# buck.net
KiCad netlist of a schematic drawn in EAGLE
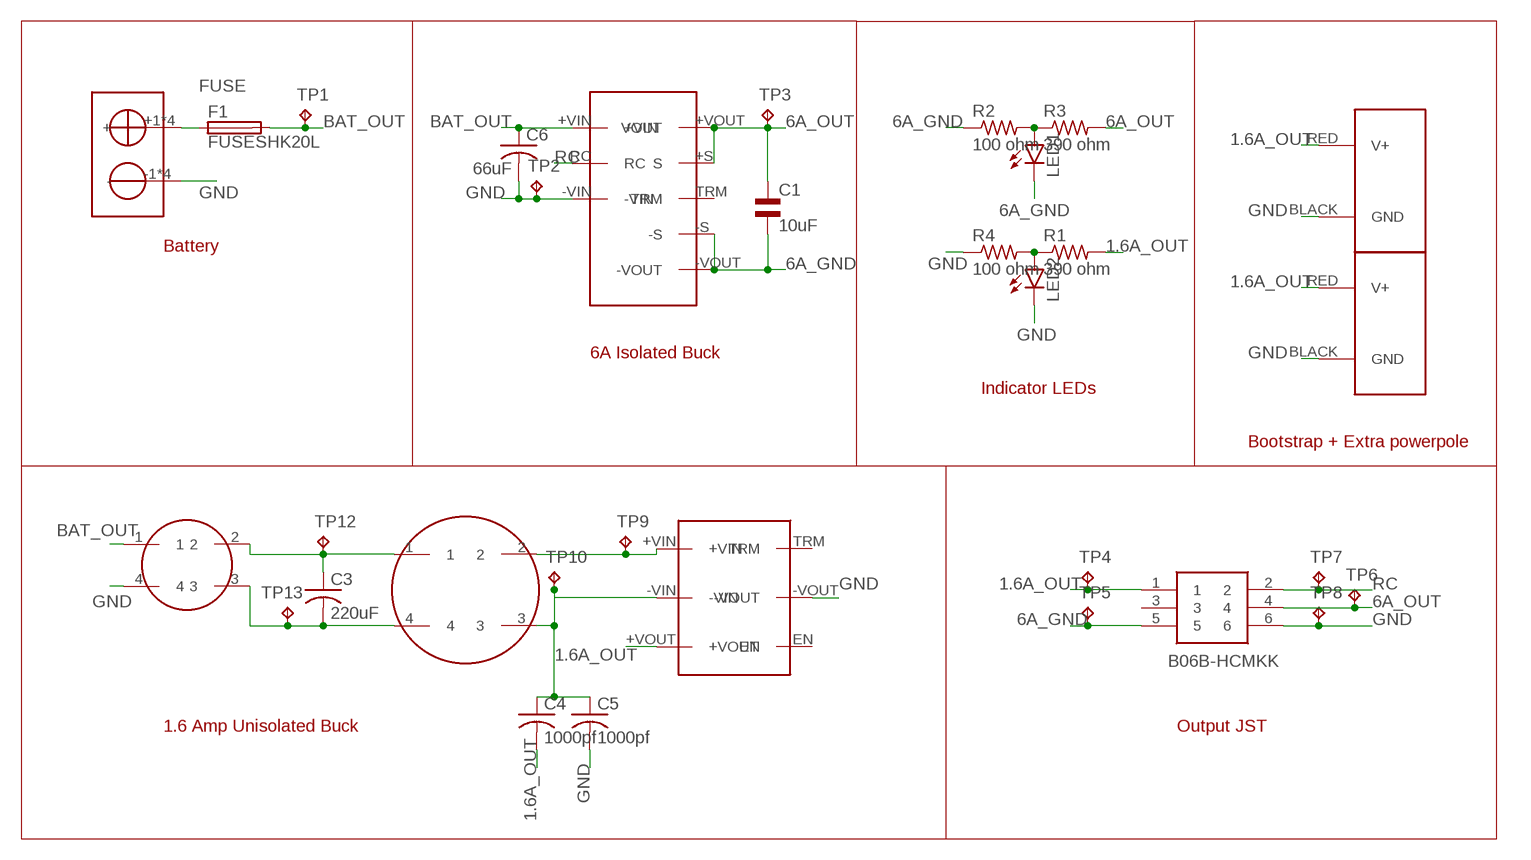
[diagram p0: schematic, sheet 1]

(export (version "E")
  (design (tool "Eeschema 10.0.6"))
  (components
    (comp (ref "BUCK150UH")
      (value "CMNMODECHOKE150UH")
      (footprint "eagle-import:CMNMODECHOKE150UH")
      (libsource (lib "eagle-import") (part "CMNMODECHOKE150UH"))
    )
    (comp (ref "C1")
      (value "10uF")
      (footprint "eagle-import:EU25-10")
      (libsource (lib "eagle-import") (part "EL-BI25-10AXIAL"))
    )
    (comp (ref "C3")
      (value "220uF")
      (footprint "eagle-import:C0805")
      (libsource (lib "eagle-import") (part "C-USC0805"))
    )
    (comp (ref "C4")
      (value "1000pf")
      (footprint "eagle-import:C0805")
      (libsource (lib "eagle-import") (part "C-USC0805"))
    )
    (comp (ref "C5")
      (value "1000pf")
      (footprint "eagle-import:C0805")
      (libsource (lib "eagle-import") (part "C-USC0805"))
    )
    (comp (ref "C6")
      (value "66uF")
      (footprint "eagle-import:C0805")
      (libsource (lib "eagle-import") (part "C-USC0805"))
    )
    (comp (ref "CHOKEME")
      (value "CMNMODECHOKE1.2MH")
      (footprint "eagle-import:CMNMODECHOKE1.2MH")
      (libsource (lib "eagle-import") (part "CMNMODECHOKE1.2MH"))
    )
    (comp (ref "F1")
      (value "FUSESHK20L")
      (footprint "eagle-import:SHK20L")
      (libsource (lib "eagle-import") (part "FUSESHK20L"))
    )
    (comp (ref "J1")
      (value "B06B-HCMKK")
      (footprint "eagle-import:B06BHCMKK")
      (fields (field (name "MOUSER_PART_NUMBER") "306-B06B-HCMKK"))
      (libsource (lib "eagle-import") (part "B06B-HCMKK"))
    )
    (comp (ref "J2")
      (value "POWERPOLE_POWER45A_DRILL")
      (footprint "eagle-import:POWERPOLE_PAIR_45A_HOLE")
      (libsource (lib "eagle-import") (part "POWERPOLE_POWER45A_DRILL"))
    )
    (comp (ref "J3")
      (value "POWERPOLE_POWER45A_DRILL")
      (footprint "eagle-import:POWERPOLE_PAIR_45A_HOLE")
      (libsource (lib "eagle-import") (part "POWERPOLE_POWER45A_DRILL"))
    )
    (comp (ref "LED1")
      (value "LEDCHIP-LED0603")
      (footprint "eagle-import:CHIP-LED0603")
      (libsource (lib "eagle-import") (part "LEDCHIP-LED0603"))
    )
    (comp (ref "LED2")
      (value "LEDCHIP-LED0603")
      (footprint "eagle-import:CHIP-LED0603")
      (libsource (lib "eagle-import") (part "LEDCHIP-LED0603"))
    )
    (comp (ref "R1")
      (value "390 ohm")
      (footprint "eagle-import:R0805")
      (libsource (lib "eagle-import") (part "R-US_R0805"))
    )
    (comp (ref "R2")
      (value "100 ohm")
      (footprint "eagle-import:R0805")
      (libsource (lib "eagle-import") (part "R-US_R0805"))
    )
    (comp (ref "R3")
      (value "390 ohm")
      (footprint "eagle-import:R0805")
      (libsource (lib "eagle-import") (part "R-US_R0805"))
    )
    (comp (ref "R4")
      (value "100 ohm")
      (footprint "eagle-import:R0805")
      (libsource (lib "eagle-import") (part "R-US_R0805"))
    )
    (comp (ref "TP1")
      (value "TPPAD1-13")
      (footprint "eagle-import:P1-13")
      (libsource (lib "eagle-import") (part "TPPAD1-13"))
    )
    (comp (ref "TP2")
      (value "TPPAD1-13")
      (footprint "eagle-import:P1-13")
      (libsource (lib "eagle-import") (part "TPPAD1-13"))
    )
    (comp (ref "TP3")
      (value "TPPAD1-13")
      (footprint "eagle-import:P1-13")
      (libsource (lib "eagle-import") (part "TPPAD1-13"))
    )
    (comp (ref "TP4")
      (value "TPPAD1-13")
      (footprint "eagle-import:P1-13")
      (libsource (lib "eagle-import") (part "TPPAD1-13"))
    )
    (comp (ref "TP5")
      (value "TPPAD1-13")
      (footprint "eagle-import:P1-13")
      (libsource (lib "eagle-import") (part "TPPAD1-13"))
    )
    (comp (ref "TP6")
      (value "TPPAD1-13")
      (footprint "eagle-import:P1-13")
      (libsource (lib "eagle-import") (part "TPPAD1-13"))
    )
    (comp (ref "TP7")
      (value "TPPAD1-13")
      (footprint "eagle-import:P1-13")
      (libsource (lib "eagle-import") (part "TPPAD1-13"))
    )
    (comp (ref "TP8")
      (value "TPPAD1-13")
      (footprint "eagle-import:P1-13")
      (libsource (lib "eagle-import") (part "TPPAD1-13"))
    )
    (comp (ref "TP9")
      (value "TPPAD1-13")
      (footprint "eagle-import:P1-13")
      (libsource (lib "eagle-import") (part "TPPAD1-13"))
    )
    (comp (ref "TP10")
      (value "TPPAD1-13")
      (footprint "eagle-import:P1-13")
      (libsource (lib "eagle-import") (part "TPPAD1-13"))
    )
    (comp (ref "TP12")
      (value "TPPAD1-13")
      (footprint "eagle-import:P1-13")
      (libsource (lib "eagle-import") (part "TPPAD1-13"))
    )
    (comp (ref "TP13")
      (value "TPPAD1-13")
      (footprint "eagle-import:P1-13")
      (libsource (lib "eagle-import") (part "TPPAD1-13"))
    )
    (comp (ref "U$1")
      (value "12V6ABUCKCONVERTER")
      (footprint "eagle-import:12V6ABUCKCONVERTER")
      (libsource (lib "eagle-import") (part "12V6ABUCKCONVERTER"))
    )
    (comp (ref "U$2")
      (value "SB50")
      (footprint "eagle-import:MINI-SB-50")
      (libsource (lib "eagle-import") (part "SB50"))
    )
    (comp (ref "U$3")
      (value "BUCK1.6A")
      (footprint "eagle-import:BUCK1.6A")
      (libsource (lib "eagle-import") (part "BUCK1.6A"))
    )
  )
  (nets
    (net (code "1") (name "/1.6A_OUT") (class "Default")
      (node (ref "C4") (pin "2") (pinfunction "2_2") (pintype "passive"))
      (node (ref "J1") (pin "1") (pinfunction "1_1") (pintype "bidirectional"))
      (node (ref "J2") (pin "RED") (pinfunction "V+_RED") (pintype "power_in"))
      (node (ref "J3") (pin "RED") (pinfunction "V+_RED") (pintype "power_in"))
      (node (ref "R1") (pin "2") (pinfunction "2_2") (pintype "passive"))
      (node (ref "TP4") (pin "TP") (pinfunction "TP_TP") (pintype "input"))
      (node (ref "U$3") (pin "+VOUT") (pinfunction "+VOUT_+VOUT") (pintype "bidirectional"))
    )
    (net (code "2") (name "/6A_GND") (class "Default")
      (node (ref "C1") (pin "2") (pinfunction "2_2") (pintype "passive"))
      (node (ref "J1") (pin "5") (pinfunction "5_5") (pintype "bidirectional"))
      (node (ref "LED1") (pin "C") (pinfunction "C_C") (pintype "passive"))
      (node (ref "R2") (pin "1") (pinfunction "1_1") (pintype "passive"))
      (node (ref "TP5") (pin "TP") (pinfunction "TP_TP") (pintype "input"))
      (node (ref "U$1") (pin "-S") (pinfunction "-S_-S") (pintype "bidirectional"))
      (node (ref "U$1") (pin "-VOUT") (pinfunction "-VOUT_-VOUT") (pintype "bidirectional"))
    )
    (net (code "3") (name "/6A_OUT") (class "Default")
      (node (ref "C1") (pin "1") (pinfunction "1_1") (pintype "passive"))
      (node (ref "J1") (pin "4") (pinfunction "4_4") (pintype "bidirectional"))
      (node (ref "R3") (pin "2") (pinfunction "2_2") (pintype "passive"))
      (node (ref "TP3") (pin "TP") (pinfunction "TP_TP") (pintype "input"))
      (node (ref "TP6") (pin "TP") (pinfunction "TP_TP") (pintype "input"))
      (node (ref "U$1") (pin "+S") (pinfunction "S_+S") (pintype "bidirectional"))
      (node (ref "U$1") (pin "+VOUT") (pinfunction "VOUT_+VOUT") (pintype "bidirectional"))
    )
    (net (code "4") (name "/BAT_OUT") (class "Default")
      (node (ref "BUCK150UH") (pin "1") (pinfunction "1_1") (pintype "bidirectional"))
      (node (ref "C6") (pin "1") (pinfunction "1_1") (pintype "passive"))
      (node (ref "F1") (pin "2A") (pinfunction "2_2A") (pintype "passive"))
      (node (ref "TP1") (pin "TP") (pinfunction "TP_TP") (pintype "input"))
      (node (ref "U$1") (pin "+VIN") (pinfunction "+VIN_+VIN") (pintype "bidirectional"))
    )
    (net (code "5") (name "/FUSE") (class "Default")
      (node (ref "F1") (pin "1A") (pinfunction "1_1A") (pintype "passive"))
      (node (ref "U$2") (pin "+1") (pinfunction "+_+1") (pintype "bidirectional"))
      (node (ref "U$2") (pin "+2") (pinfunction "+_+2") (pintype "bidirectional"))
      (node (ref "U$2") (pin "+3") (pinfunction "+_+3") (pintype "bidirectional"))
      (node (ref "U$2") (pin "+4") (pinfunction "+_+4") (pintype "bidirectional"))
    )
    (net (code "6") (name "/GND") (class "Default")
      (node (ref "BUCK150UH") (pin "4") (pinfunction "4_4") (pintype "bidirectional"))
      (node (ref "C5") (pin "2") (pinfunction "2_2") (pintype "passive"))
      (node (ref "C6") (pin "2") (pinfunction "2_2") (pintype "passive"))
      (node (ref "J1") (pin "6") (pinfunction "6_6") (pintype "bidirectional"))
      (node (ref "J2") (pin "BLACK") (pinfunction "GND_BLACK") (pintype "power_in"))
      (node (ref "J3") (pin "BLACK") (pinfunction "GND_BLACK") (pintype "power_in"))
      (node (ref "LED2") (pin "C") (pinfunction "C_C") (pintype "passive"))
      (node (ref "R4") (pin "1") (pinfunction "1_1") (pintype "passive"))
      (node (ref "TP2") (pin "TP") (pinfunction "TP_TP") (pintype "input"))
      (node (ref "TP8") (pin "TP") (pinfunction "TP_TP") (pintype "input"))
      (node (ref "U$1") (pin "-VIN") (pinfunction "-VIN_-VIN") (pintype "bidirectional"))
      (node (ref "U$2") (pin "-1") (pinfunction "-_-1") (pintype "bidirectional"))
      (node (ref "U$2") (pin "-2") (pinfunction "-_-2") (pintype "bidirectional"))
      (node (ref "U$2") (pin "-3") (pinfunction "-_-3") (pintype "bidirectional"))
      (node (ref "U$2") (pin "-4") (pinfunction "-_-4") (pintype "bidirectional"))
      (node (ref "U$3") (pin "-VOUT") (pinfunction "-VOUT_-VOUT") (pintype "bidirectional"))
    )
    (net (code "7") (name "/RC") (class "Default")
      (node (ref "J1") (pin "2") (pinfunction "2_2") (pintype "bidirectional"))
      (node (ref "TP7") (pin "TP") (pinfunction "TP_TP") (pintype "input"))
      (node (ref "U$1") (pin "RC") (pinfunction "RC_RC") (pintype "bidirectional"))
    )
    (net (code "8") (name "Net-(BUCK150UH-Pad2)") (class "Default")
      (node (ref "BUCK150UH") (pin "2") (pinfunction "2_2") (pintype "bidirectional"))
      (node (ref "C3") (pin "1") (pinfunction "1_1") (pintype "passive"))
      (node (ref "CHOKEME") (pin "1") (pinfunction "1_1") (pintype "bidirectional"))
      (node (ref "TP12") (pin "TP") (pinfunction "TP_TP") (pintype "input"))
    )
    (net (code "9") (name "Net-(BUCK150UH-Pad3)") (class "Default")
      (node (ref "BUCK150UH") (pin "3") (pinfunction "3_3") (pintype "bidirectional"))
      (node (ref "C3") (pin "2") (pinfunction "2_2") (pintype "passive"))
      (node (ref "CHOKEME") (pin "4") (pinfunction "4_4") (pintype "bidirectional"))
      (node (ref "TP13") (pin "TP") (pinfunction "TP_TP") (pintype "input"))
    )
    (net (code "10") (name "Net-(C4-Pad1)") (class "Default")
      (node (ref "C4") (pin "1") (pinfunction "1_1") (pintype "passive"))
      (node (ref "C5") (pin "1") (pinfunction "1_1") (pintype "passive"))
      (node (ref "CHOKEME") (pin "3") (pinfunction "3_3") (pintype "bidirectional"))
      (node (ref "TP10") (pin "TP") (pinfunction "TP_TP") (pintype "input"))
      (node (ref "U$3") (pin "-VIN") (pinfunction "-VIN_-VIN") (pintype "bidirectional"))
    )
    (net (code "11") (name "Net-(CHOKEME-Pad2)") (class "Default")
      (node (ref "CHOKEME") (pin "2") (pinfunction "2_2") (pintype "bidirectional"))
      (node (ref "TP9") (pin "TP") (pinfunction "TP_TP") (pintype "input"))
      (node (ref "U$3") (pin "+VIN") (pinfunction "+VIN_+VIN") (pintype "bidirectional"))
    )
    (net (code "12") (name "Net-(LED1-PadA)") (class "Default")
      (node (ref "LED1") (pin "A") (pinfunction "A_A") (pintype "passive"))
      (node (ref "R2") (pin "2") (pinfunction "2_2") (pintype "passive"))
      (node (ref "R3") (pin "1") (pinfunction "1_1") (pintype "passive"))
    )
    (net (code "13") (name "Net-(LED2-PadA)") (class "Default")
      (node (ref "LED2") (pin "A") (pinfunction "A_A") (pintype "passive"))
      (node (ref "R1") (pin "1") (pinfunction "1_1") (pintype "passive"))
      (node (ref "R4") (pin "2") (pinfunction "2_2") (pintype "passive"))
    )
    (net (code "14") (name "unconnected-(J1-Pad3)") (class "Default")
      (node (ref "J1") (pin "3") (pinfunction "3_3") (pintype "bidirectional"))
    )
    (net (code "15") (name "unconnected-(U$1-PadTRM)") (class "Default")
      (node (ref "U$1") (pin "TRM") (pinfunction "TRM_TRM") (pintype "bidirectional"))
    )
    (net (code "16") (name "unconnected-(U$3-PadEN)") (class "Default")
      (node (ref "U$3") (pin "EN") (pinfunction "EN_EN") (pintype "bidirectional"))
    )
    (net (code "17") (name "unconnected-(U$3-PadTRM)") (class "Default")
      (node (ref "U$3") (pin "TRM") (pinfunction "TRM_TRM") (pintype "bidirectional"))
    )
  )
)
